# Keyboard.net
KiCad netlist of a schematic drawn in Altium Designer
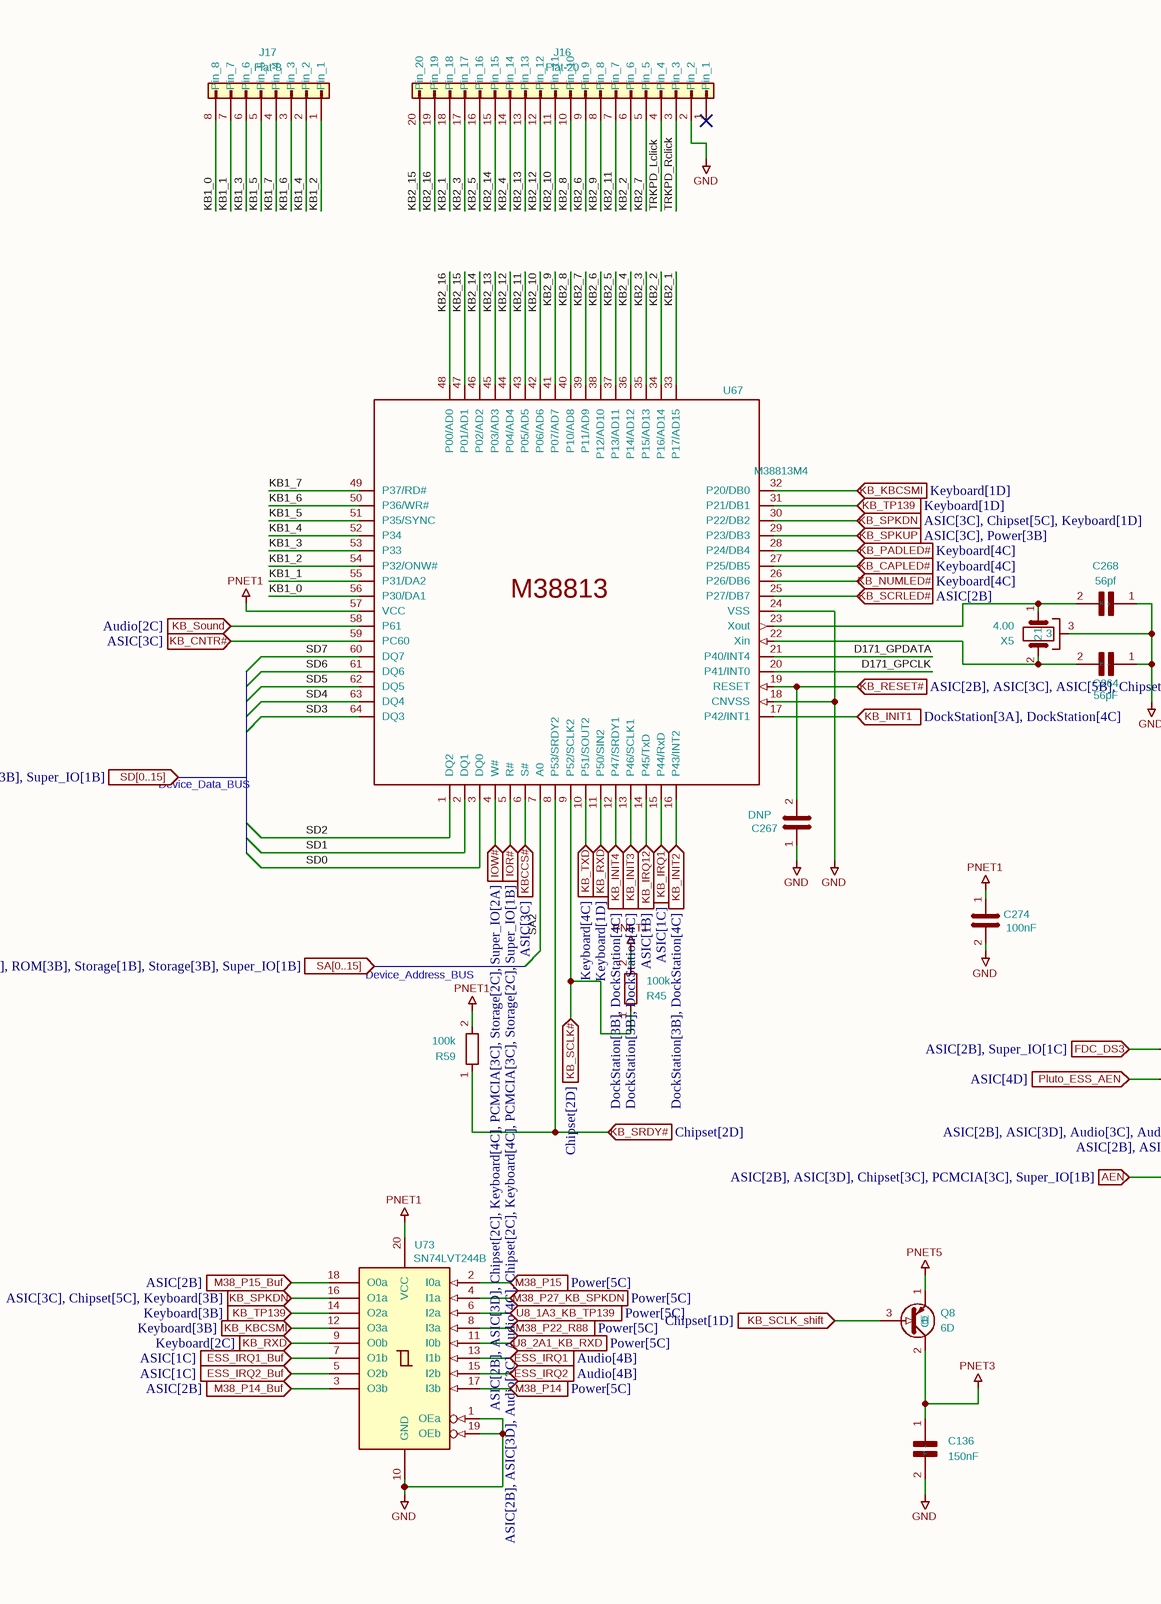
[diagram p0: Keyboard.SchDoc, left]
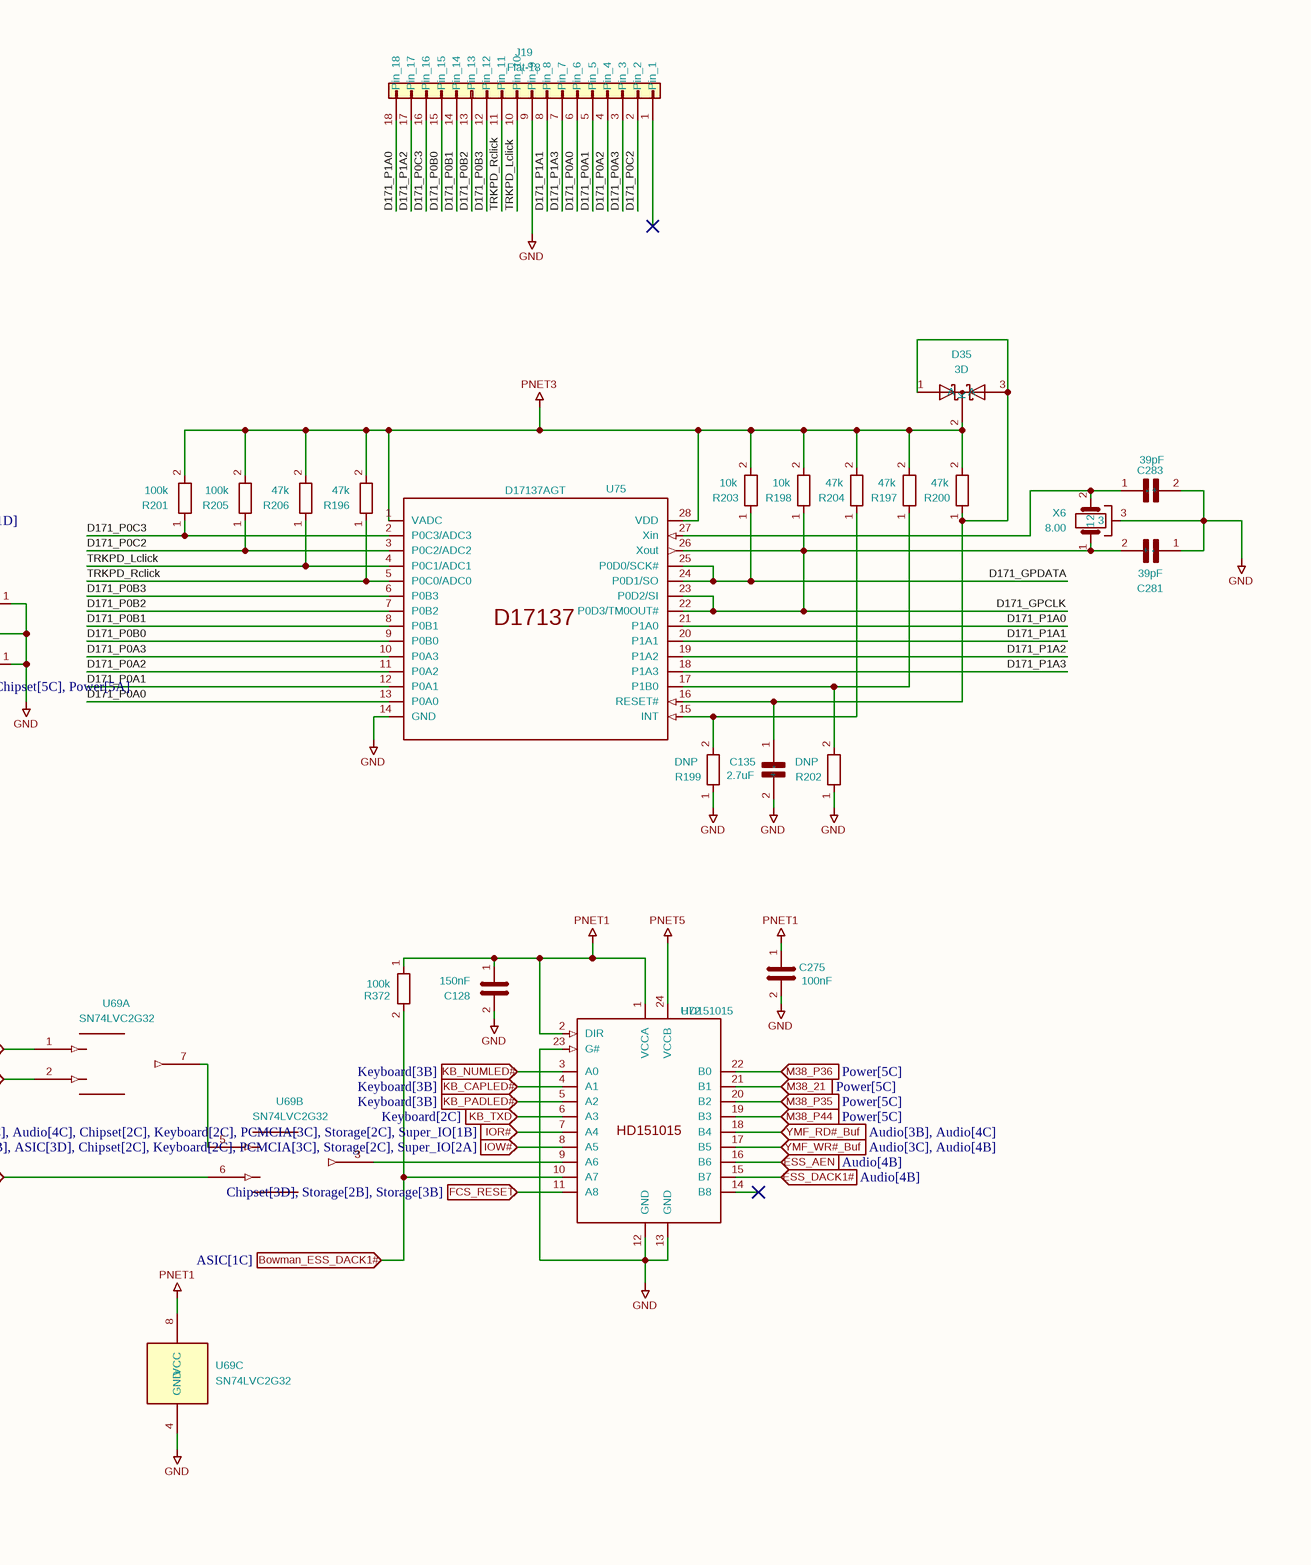
[diagram p1: Keyboard.SchDoc, right]

(export (version "E")
  (design (tool "Eeschema 10.0.6"))
  (components
    (comp (ref "C128") (value "150nF") (footprint "C_0402_1005Metric") (libsource (lib "Device") (part "C")))
    (comp (ref "C135") (value "2.7uF") (footprint "C_0805_2012Metric") (libsource (lib "") (part "C_1")))
    (comp (ref "C136")
      (value "150nF")
      (footprint "C_0402_1005Metric")
      (libsource (lib "PCM_Elektuur") (part "C"))
    )
    (comp (ref "C264") (value "56pF") (footprint "C_0402_1005Metric") (libsource (lib "") (part "C_1")))
    (comp (ref "C267") (value "DNP") (footprint "C_0402_1005Metric") (libsource (lib "Device") (part "C")))
    (comp (ref "C268")
      (value "56pf")
      (footprint "C_0402_1005Metric")
      (libsource (lib "PCM_Elektuur") (part "C"))
    )
    (comp (ref "C274") (value "100nF") (footprint "C_0402_1005Metric") (libsource (lib "Device") (part "C")))
    (comp (ref "C275") (value "100nF") (footprint "C_0402_1005Metric") (libsource (lib "Device") (part "C")))
    (comp (ref "C281") (value "39pF") (footprint "C_0402_1005Metric") (libsource (lib "") (part "C_1")))
    (comp (ref "C283") (value "39pF") (footprint "C_0402_1005Metric") (libsource (lib "") (part "C_2")))
    (comp (ref "D35")
      (value "3D")
      (footprint "3D")
      (libsource (lib "Device") (part "D_Schottky_Dual_CommonCathode_AKA"))
    )
    (comp (ref "J16")
      (value "Flat-20")
      (footprint "Flat-20")
      (libsource (lib "Connector_Generic") (part "Conn_01x20"))
    )
    (comp (ref "J17")
      (value "Flat-8")
      (footprint "Flat-8")
      (libsource (lib "Connector_Generic") (part "Conn_01x08"))
    )
    (comp (ref "J19")
      (value "Flat-18")
      (footprint "Flat-18")
      (libsource (lib "Connector_Generic") (part "Conn_01x18"))
    )
    (comp (ref "Q8")
      (value "6D")
      (footprint "3D")
      (libsource (lib "PCM_Transistor_BJT_AKL") (part "Q_PNP_Generic_ECB"))
    )
    (comp (ref "R45") (value "100k") (footprint "R_0402_1005Metric") (libsource (lib "") (part "R_1")))
    (comp (ref "R59") (value "100k") (footprint "R_0402_1005Metric") (libsource (lib "Device") (part "R")))
    (comp (ref "R196") (value "47k") (footprint "R_0402_1005Metric") (libsource (lib "Device") (part "R")))
    (comp (ref "R197") (value "47k") (footprint "R_0402_1005Metric") (libsource (lib "Device") (part "R")))
    (comp (ref "R198") (value "10k") (footprint "R_0402_1005Metric") (libsource (lib "Device") (part "R")))
    (comp (ref "R199") (value "DNP") (footprint "R_0402_1005Metric") (libsource (lib "Device") (part "R")))
    (comp (ref "R200") (value "47k") (footprint "R_0402_1005Metric") (libsource (lib "Device") (part "R")))
    (comp (ref "R201") (value "100k") (footprint "R_0402_1005Metric") (libsource (lib "Device") (part "R")))
    (comp (ref "R202") (value "DNP") (footprint "R_0402_1005Metric") (libsource (lib "Device") (part "R")))
    (comp (ref "R203") (value "10k") (footprint "R_0402_1005Metric") (libsource (lib "Device") (part "R")))
    (comp (ref "R204") (value "47k") (footprint "R_0402_1005Metric") (libsource (lib "Device") (part "R")))
    (comp (ref "R205") (value "100k") (footprint "R_0402_1005Metric") (libsource (lib "Device") (part "R")))
    (comp (ref "R206") (value "47k") (footprint "R_0402_1005Metric") (libsource (lib "Device") (part "R")))
    (comp (ref "R372") (value "100k") (footprint "R_0402_1005Metric") (libsource (lib "") (part "R_2")))
    (comp (ref "U67") (value "M38813M4") (footprint "QFN64") (libsource (lib "PC110") (part "M38813")))
    (comp (ref "U69")
      (value "SN74LVC2G32")
      (footprint "SSOP-8_2.95x2.8mm_P0.65mm")
      (libsource (lib "74xGxx") (part "74LVC2G32"))
    )
    (comp (ref "U72")
      (value "HD151015")
      (footprint "SSOP-24_5.3x8.2mm_P0.65mm")
      (libsource (lib "PC110") (part "HD151015"))
    )
    (comp (ref "U73")
      (value "SN74LVT244B")
      (footprint "TSSOP-20_4.4x6.5mm_P0.65mm")
      (libsource (lib "74xx") (part "74LS244"))
    )
    (comp (ref "U75") (value "D17137AGT") (footprint "SSOP-28") (libsource (lib "PC110") (part "D17137")))
    (comp (ref "X5") (value "4.00") (footprint "XTAL-5") (libsource (lib "") (part "Crystal_GND3_1")))
    (comp (ref "X6") (value "8.00") (footprint "XTAL-4") (libsource (lib "Device") (part "Crystal_GND3")))
  )
  (nets
    (net (code "24") (name "/AEN") (class "Default")
      (node (ref "U69") (pin "6") (pinfunction "6_6") (pintype "input"))
    )
    (net (code "25") (name "/Bowman_ESS_DACK1#") (class "Default")
      (node (ref "R372") (pin "2") (pinfunction "2_2") (pintype "passive"))
      (node (ref "U72") (pin "10") (pinfunction "A7_10") (pintype "bidirectional"))
    )
    (net (code "26") (name "/D171_GPCLK") (class "Default")
      (node (ref "C281") (pin "2") (pinfunction "-_2") (pintype "passive"))
      (node (ref "R198") (pin "1") (pinfunction "1_1") (pintype "passive"))
      (node (ref "U67") (pin "20") (pinfunction "P41/INT0_20") (pintype "bidirectional"))
      (node (ref "U75") (pin "22") (pinfunction "P0D3/TM0OUT#_22") (pintype "bidirectional"))
      (node (ref "U75") (pin "23") (pinfunction "P0D2/SI_23") (pintype "bidirectional"))
      (node (ref "U75") (pin "26") (pinfunction "Xout_26") (pintype "output"))
      (node (ref "X6") (pin "1") (pinfunction "1_1") (pintype "passive"))
    )
    (net (code "27") (name "/D171_GPDATA") (class "Default")
      (node (ref "R203") (pin "1") (pinfunction "1_1") (pintype "passive"))
      (node (ref "U67") (pin "21") (pinfunction "P40/INT4_21") (pintype "bidirectional"))
      (node (ref "U75") (pin "24") (pinfunction "P0D1/SO_24") (pintype "bidirectional"))
      (node (ref "U75") (pin "25") (pinfunction "P0D0/SCK#_25") (pintype "bidirectional"))
    )
    (net (code "28") (name "/D171_P0A0") (class "Default")
      (node (ref "J19") (pin "6") (pinfunction "Pin_6_6") (pintype "passive"))
      (node (ref "U75") (pin "13") (pinfunction "P0A0_13") (pintype "bidirectional"))
    )
    (net (code "29") (name "/D171_P0A1") (class "Default")
      (node (ref "J19") (pin "5") (pinfunction "Pin_5_5") (pintype "passive"))
      (node (ref "U75") (pin "12") (pinfunction "P0A1_12") (pintype "bidirectional"))
    )
    (net (code "30") (name "/D171_P0A2") (class "Default")
      (node (ref "J19") (pin "4") (pinfunction "Pin_4_4") (pintype "passive"))
      (node (ref "U75") (pin "11") (pinfunction "P0A2_11") (pintype "bidirectional"))
    )
    (net (code "31") (name "/D171_P0A3") (class "Default")
      (node (ref "J19") (pin "3") (pinfunction "Pin_3_3") (pintype "passive"))
      (node (ref "U75") (pin "10") (pinfunction "P0A3_10") (pintype "bidirectional"))
    )
    (net (code "32") (name "/D171_P0B0") (class "Default")
      (node (ref "J19") (pin "15") (pinfunction "Pin_15_15") (pintype "passive"))
      (node (ref "U75") (pin "9") (pinfunction "P0B0_9") (pintype "bidirectional"))
    )
    (net (code "33") (name "/D171_P0B1") (class "Default")
      (node (ref "J19") (pin "14") (pinfunction "Pin_14_14") (pintype "passive"))
      (node (ref "U75") (pin "8") (pinfunction "P0B1_8") (pintype "bidirectional"))
    )
    (net (code "34") (name "/D171_P0B2") (class "Default")
      (node (ref "J19") (pin "13") (pinfunction "Pin_13_13") (pintype "passive"))
      (node (ref "U75") (pin "7") (pinfunction "P0B2_7") (pintype "bidirectional"))
    )
    (net (code "35") (name "/D171_P0B3") (class "Default")
      (node (ref "J19") (pin "12") (pinfunction "Pin_12_12") (pintype "passive"))
      (node (ref "U75") (pin "6") (pinfunction "P0B3_6") (pintype "bidirectional"))
    )
    (net (code "36") (name "/D171_P0C2") (class "Default")
      (node (ref "J19") (pin "2") (pinfunction "Pin_2_2") (pintype "passive"))
      (node (ref "R205") (pin "1") (pinfunction "1_1") (pintype "passive"))
      (node (ref "U75") (pin "3") (pinfunction "P0C2/ADC2_3") (pintype "bidirectional"))
    )
    (net (code "37") (name "/D171_P0C3") (class "Default")
      (node (ref "J19") (pin "16") (pinfunction "Pin_16_16") (pintype "passive"))
      (node (ref "R201") (pin "1") (pinfunction "1_1") (pintype "passive"))
      (node (ref "U75") (pin "2") (pinfunction "P0C3/ADC3_2") (pintype "bidirectional"))
    )
    (net (code "38") (name "/D171_P1A0") (class "Default")
      (node (ref "J19") (pin "18") (pinfunction "Pin_18_18") (pintype "passive"))
      (node (ref "U75") (pin "21") (pinfunction "P1A0_21") (pintype "bidirectional"))
    )
    (net (code "39") (name "/D171_P1A1") (class "Default")
      (node (ref "J19") (pin "8") (pinfunction "Pin_8_8") (pintype "passive"))
      (node (ref "U75") (pin "20") (pinfunction "P1A1_20") (pintype "bidirectional"))
    )
    (net (code "40") (name "/D171_P1A2") (class "Default")
      (node (ref "J19") (pin "17") (pinfunction "Pin_17_17") (pintype "passive"))
      (node (ref "U75") (pin "19") (pinfunction "P1A2_19") (pintype "bidirectional"))
    )
    (net (code "41") (name "/D171_P1A3") (class "Default")
      (node (ref "J19") (pin "7") (pinfunction "Pin_7_7") (pintype "passive"))
      (node (ref "U75") (pin "18") (pinfunction "P1A3_18") (pintype "bidirectional"))
    )
    (net (code "42") (name "/ESS_AEN") (class "Default")
      (node (ref "U72") (pin "16") (pinfunction "B6_16") (pintype "bidirectional"))
    )
    (net (code "43") (name "/ESS_DACK1#") (class "Default")
      (node (ref "U72") (pin "15") (pinfunction "B7_15") (pintype "bidirectional"))
    )
    (net (code "44") (name "/ESS_IRQ1") (class "Default")
      (node (ref "U73") (pin "13") (pinfunction "I1b_13") (pintype "input"))
    )
    (net (code "45") (name "/ESS_IRQ1_Buf") (class "Default")
      (node (ref "U73") (pin "7") (pinfunction "O1b_7") (pintype "tri_state"))
    )
    (net (code "46") (name "/ESS_IRQ2") (class "Default")
      (node (ref "U73") (pin "15") (pinfunction "I2b_15") (pintype "input"))
    )
    (net (code "47") (name "/ESS_IRQ2_Buf") (class "Default")
      (node (ref "U73") (pin "5") (pinfunction "O2b_5") (pintype "tri_state"))
    )
    (net (code "48") (name "/FCS_RESET") (class "Default")
      (node (ref "U72") (pin "11") (pinfunction "A8_11") (pintype "bidirectional"))
    )
    (net (code "49") (name "/FDC_DS3") (class "Default")
      (node (ref "U69") (pin "1") (pinfunction "1_1") (pintype "input"))
    )
    (net (code "50") (name "/IOR#") (class "Default")
      (node (ref "U67") (pin "5") (pinfunction "R#_5") (pintype "bidirectional"))
      (node (ref "U72") (pin "7") (pinfunction "A4_7") (pintype "bidirectional"))
    )
    (net (code "51") (name "/IOW#") (class "Default")
      (node (ref "U67") (pin "4") (pinfunction "W#_4") (pintype "bidirectional"))
      (node (ref "U72") (pin "8") (pinfunction "A5_8") (pintype "bidirectional"))
    )
    (net (code "52") (name "/KB1_0") (class "Default")
      (node (ref "J17") (pin "8") (pinfunction "Pin_8_8") (pintype "passive"))
      (node (ref "U67") (pin "56") (pinfunction "P30/DA1_56") (pintype "bidirectional"))
    )
    (net (code "53") (name "/KB1_1") (class "Default")
      (node (ref "J17") (pin "7") (pinfunction "Pin_7_7") (pintype "passive"))
      (node (ref "U67") (pin "55") (pinfunction "P31/DA2_55") (pintype "bidirectional"))
    )
    (net (code "54") (name "/KB1_2") (class "Default")
      (node (ref "J17") (pin "1") (pinfunction "Pin_1_1") (pintype "passive"))
      (node (ref "U67") (pin "54") (pinfunction "P32/ONW#_54") (pintype "bidirectional"))
    )
    (net (code "55") (name "/KB1_3") (class "Default")
      (node (ref "J17") (pin "6") (pinfunction "Pin_6_6") (pintype "passive"))
      (node (ref "U67") (pin "53") (pinfunction "P33_53") (pintype "bidirectional"))
    )
    (net (code "56") (name "/KB1_4") (class "Default")
      (node (ref "J17") (pin "2") (pinfunction "Pin_2_2") (pintype "passive"))
      (node (ref "U67") (pin "52") (pinfunction "P34_52") (pintype "bidirectional"))
    )
    (net (code "57") (name "/KB1_5") (class "Default")
      (node (ref "J17") (pin "5") (pinfunction "Pin_5_5") (pintype "passive"))
      (node (ref "U67") (pin "51") (pinfunction "P35/SYNC_51") (pintype "bidirectional"))
    )
    (net (code "58") (name "/KB1_6") (class "Default")
      (node (ref "J17") (pin "3") (pinfunction "Pin_3_3") (pintype "passive"))
      (node (ref "U67") (pin "50") (pinfunction "P36/WR#_50") (pintype "bidirectional"))
    )
    (net (code "59") (name "/KB1_7") (class "Default")
      (node (ref "J17") (pin "4") (pinfunction "Pin_4_4") (pintype "passive"))
      (node (ref "U67") (pin "49") (pinfunction "P37/RD#_49") (pintype "bidirectional"))
    )
    (net (code "60") (name "/KB2_1") (class "Default")
      (node (ref "J16") (pin "18") (pinfunction "Pin_18_18") (pintype "passive"))
      (node (ref "U67") (pin "33") (pinfunction "P17/AD15_33") (pintype "bidirectional"))
    )
    (net (code "61") (name "/KB2_2") (class "Default")
      (node (ref "J16") (pin "6") (pinfunction "Pin_6_6") (pintype "passive"))
      (node (ref "U67") (pin "34") (pinfunction "P16/AD14_34") (pintype "bidirectional"))
    )
    (net (code "62") (name "/KB2_3") (class "Default")
      (node (ref "J16") (pin "17") (pinfunction "Pin_17_17") (pintype "passive"))
      (node (ref "U67") (pin "35") (pinfunction "P15/AD13_35") (pintype "bidirectional"))
    )
    (net (code "63") (name "/KB2_4") (class "Default")
      (node (ref "J16") (pin "14") (pinfunction "Pin_14_14") (pintype "passive"))
      (node (ref "U67") (pin "36") (pinfunction "P14/AD12_36") (pintype "bidirectional"))
    )
    (net (code "64") (name "/KB2_5") (class "Default")
      (node (ref "J16") (pin "16") (pinfunction "Pin_16_16") (pintype "passive"))
      (node (ref "U67") (pin "37") (pinfunction "P13/AD11_37") (pintype "bidirectional"))
    )
    (net (code "65") (name "/KB2_6") (class "Default")
      (node (ref "J16") (pin "9") (pinfunction "Pin_9_9") (pintype "passive"))
      (node (ref "U67") (pin "38") (pinfunction "P12/AD10_38") (pintype "bidirectional"))
    )
    (net (code "66") (name "/KB2_7") (class "Default")
      (node (ref "J16") (pin "5") (pinfunction "Pin_5_5") (pintype "passive"))
      (node (ref "U67") (pin "39") (pinfunction "P11/AD9_39") (pintype "bidirectional"))
    )
    (net (code "67") (name "/KB2_8") (class "Default")
      (node (ref "J16") (pin "10") (pinfunction "Pin_10_10") (pintype "passive"))
      (node (ref "U67") (pin "40") (pinfunction "P10/AD8_40") (pintype "bidirectional"))
    )
    (net (code "68") (name "/KB2_9") (class "Default")
      (node (ref "J16") (pin "8") (pinfunction "Pin_8_8") (pintype "passive"))
      (node (ref "U67") (pin "41") (pinfunction "P07/AD7_41") (pintype "bidirectional"))
    )
    (net (code "69") (name "/KB2_10") (class "Default")
      (node (ref "J16") (pin "11") (pinfunction "Pin_11_11") (pintype "passive"))
      (node (ref "U67") (pin "42") (pinfunction "P06/AD6_42") (pintype "bidirectional"))
    )
    (net (code "70") (name "/KB2_11") (class "Default")
      (node (ref "J16") (pin "7") (pinfunction "Pin_7_7") (pintype "passive"))
      (node (ref "U67") (pin "43") (pinfunction "P05/AD5_43") (pintype "bidirectional"))
    )
    (net (code "71") (name "/KB2_12") (class "Default")
      (node (ref "J16") (pin "12") (pinfunction "Pin_12_12") (pintype "passive"))
      (node (ref "U67") (pin "44") (pinfunction "P04/AD4_44") (pintype "bidirectional"))
    )
    (net (code "72") (name "/KB2_13") (class "Default")
      (node (ref "J16") (pin "13") (pinfunction "Pin_13_13") (pintype "passive"))
      (node (ref "U67") (pin "45") (pinfunction "P03/AD3_45") (pintype "bidirectional"))
    )
    (net (code "73") (name "/KB2_14") (class "Default")
      (node (ref "J16") (pin "15") (pinfunction "Pin_15_15") (pintype "passive"))
      (node (ref "U67") (pin "46") (pinfunction "P02/AD2_46") (pintype "bidirectional"))
    )
    (net (code "74") (name "/KB2_15") (class "Default")
      (node (ref "J16") (pin "20") (pinfunction "Pin_20_20") (pintype "passive"))
      (node (ref "U67") (pin "47") (pinfunction "P01/AD1_47") (pintype "bidirectional"))
    )
    (net (code "75") (name "/KB2_16") (class "Default")
      (node (ref "J16") (pin "19") (pinfunction "Pin_19_19") (pintype "passive"))
      (node (ref "U67") (pin "48") (pinfunction "P00/AD0_48") (pintype "bidirectional"))
    )
    (net (code "76") (name "/KBCCS#") (class "Default")
      (node (ref "U67") (pin "6") (pinfunction "S#_6") (pintype "bidirectional"))
    )
    (net (code "77") (name "/KB_CAPLED#") (class "Default")
      (node (ref "U67") (pin "27") (pinfunction "P25/DB5_27") (pintype "bidirectional"))
      (node (ref "U72") (pin "4") (pinfunction "A1_4") (pintype "bidirectional"))
    )
    (net (code "78") (name "/KB_CNTR#") (class "Default")
      (node (ref "U67") (pin "59") (pinfunction "PC60_59") (pintype "bidirectional"))
    )
    (net (code "79") (name "/KB_INIT1") (class "Default")
      (node (ref "U67") (pin "17") (pinfunction "P42/INT1_17") (pintype "bidirectional"))
    )
    (net (code "80") (name "/KB_INIT2") (class "Default")
      (node (ref "U67") (pin "16") (pinfunction "P43/INT2_16") (pintype "bidirectional"))
    )
    (net (code "81") (name "/KB_INIT3") (class "Default")
      (node (ref "U67") (pin "13") (pinfunction "P46/SCLK1_13") (pintype "bidirectional"))
    )
    (net (code "82") (name "/KB_INIT4") (class "Default")
      (node (ref "U67") (pin "12") (pinfunction "P47/SRDY1_12") (pintype "bidirectional"))
    )
    (net (code "83") (name "/KB_IRQ1") (class "Default")
      (node (ref "U67") (pin "15") (pinfunction "P44/RxD_15") (pintype "bidirectional"))
    )
    (net (code "84") (name "/KB_IRQ12") (class "Default")
      (node (ref "U67") (pin "14") (pinfunction "P45/TxD_14") (pintype "bidirectional"))
    )
    (net (code "85") (name "/KB_KBCSMI") (class "Default")
      (node (ref "U67") (pin "32") (pinfunction "P20/DB0_32") (pintype "bidirectional"))
      (node (ref "U73") (pin "12") (pinfunction "O3a_12") (pintype "tri_state"))
    )
    (net (code "86") (name "/KB_NUMLED#") (class "Default")
      (node (ref "U67") (pin "26") (pinfunction "P26/DB6_26") (pintype "bidirectional"))
      (node (ref "U72") (pin "3") (pinfunction "A0_3") (pintype "bidirectional"))
    )
    (net (code "87") (name "/KB_PADLED#") (class "Default")
      (node (ref "U67") (pin "28") (pinfunction "P24/DB4_28") (pintype "bidirectional"))
      (node (ref "U72") (pin "5") (pinfunction "A2_5") (pintype "bidirectional"))
    )
    (net (code "88") (name "/KB_RESET#") (class "Default")
      (node (ref "C267") (pin "2") (pinfunction "2_2") (pintype "passive"))
      (node (ref "U67") (pin "19") (pinfunction "RESET_19") (pintype "input"))
    )
    (net (code "89") (name "/KB_RXD") (class "Default")
      (node (ref "U67") (pin "11") (pinfunction "P50/SIN2_11") (pintype "bidirectional"))
      (node (ref "U73") (pin "9") (pinfunction "O0b_9") (pintype "tri_state"))
    )
    (net (code "90") (name "/KB_SCLK#") (class "Default")
      (node (ref "R45") (pin "1") (pinfunction "1_1") (pintype "passive"))
      (node (ref "U67") (pin "9") (pinfunction "P52/SCLK2_9") (pintype "bidirectional"))
    )
    (net (code "91") (name "/KB_SCLK_shift") (class "Default")
      (node (ref "Q8") (pin "3") (pinfunction "B_3") (pintype "input"))
    )
    (net (code "92") (name "/KB_SCRLED#") (class "Default")
      (node (ref "U67") (pin "25") (pinfunction "P27/DB7_25") (pintype "bidirectional"))
    )
    (net (code "93") (name "/KB_SPKDN") (class "Default")
      (node (ref "U67") (pin "30") (pinfunction "P22/DB2_30") (pintype "bidirectional"))
      (node (ref "U73") (pin "16") (pinfunction "O1a_16") (pintype "tri_state"))
    )
    (net (code "94") (name "/KB_SPKUP") (class "Default")
      (node (ref "U67") (pin "29") (pinfunction "P23/DB3_29") (pintype "bidirectional"))
    )
    (net (code "95") (name "/KB_SRDY#") (class "Default")
      (node (ref "R59") (pin "1") (pinfunction "1_1") (pintype "passive"))
      (node (ref "U67") (pin "8") (pinfunction "P53/SRDY2_8") (pintype "bidirectional"))
    )
    (net (code "96") (name "/KB_Sound") (class "Default")
      (node (ref "U67") (pin "58") (pinfunction "P61_58") (pintype "bidirectional"))
    )
    (net (code "97") (name "/KB_TP139") (class "Default")
      (node (ref "U67") (pin "31") (pinfunction "P21/DB1_31") (pintype "bidirectional"))
      (node (ref "U73") (pin "14") (pinfunction "O2a_14") (pintype "tri_state"))
    )
    (net (code "98") (name "/KB_TXD") (class "Default")
      (node (ref "U67") (pin "10") (pinfunction "P51/SOUT2_10") (pintype "bidirectional"))
      (node (ref "U72") (pin "6") (pinfunction "A3_6") (pintype "bidirectional"))
    )
    (net (code "99") (name "/M38_21") (class "Default")
      (node (ref "U72") (pin "21") (pinfunction "B1_21") (pintype "bidirectional"))
    )
    (net (code "100") (name "/M38_P14") (class "Default")
      (node (ref "U73") (pin "17") (pinfunction "I3b_17") (pintype "input"))
    )
    (net (code "101") (name "/M38_P14_Buf") (class "Default")
      (node (ref "U73") (pin "3") (pinfunction "O3b_3") (pintype "tri_state"))
    )
    (net (code "102") (name "/M38_P15") (class "Default")
      (node (ref "U73") (pin "2") (pinfunction "I0a_2") (pintype "input"))
    )
    (net (code "103") (name "/M38_P15_Buf") (class "Default")
      (node (ref "U73") (pin "18") (pinfunction "O0a_18") (pintype "tri_state"))
    )
    (net (code "104") (name "/M38_P22_R88") (class "Default")
      (node (ref "U73") (pin "8") (pinfunction "I3a_8") (pintype "input"))
    )
    (net (code "105") (name "/M38_P27_KB_SPKDN") (class "Default")
      (node (ref "U73") (pin "4") (pinfunction "I1a_4") (pintype "input"))
    )
    (net (code "106") (name "/M38_P35") (class "Default")
      (node (ref "U72") (pin "20") (pinfunction "B2_20") (pintype "bidirectional"))
    )
    (net (code "107") (name "/M38_P36") (class "Default")
      (node (ref "U72") (pin "22") (pinfunction "B0_22") (pintype "bidirectional"))
    )
    (net (code "108") (name "/M38_P44") (class "Default")
      (node (ref "U72") (pin "19") (pinfunction "B3_19") (pintype "bidirectional"))
    )
    (net (code "109") (name "/Pluto_ESS_AEN") (class "Default")
      (node (ref "U69") (pin "2") (pinfunction "2_2") (pintype "input"))
    )
    (net (code "110") (name "/SA2") (class "Default")
      (node (ref "U67") (pin "7") (pinfunction "A0_7") (pintype "bidirectional"))
    )
    (net (code "112") (name "/SD0") (class "Default")
      (node (ref "U67") (pin "3") (pinfunction "DQ0_3") (pintype "bidirectional"))
    )
    (net (code "113") (name "/SD1") (class "Default")
      (node (ref "U67") (pin "2") (pinfunction "DQ1_2") (pintype "bidirectional"))
    )
    (net (code "114") (name "/SD2") (class "Default")
      (node (ref "U67") (pin "1") (pinfunction "DQ2_1") (pintype "bidirectional"))
    )
    (net (code "115") (name "/SD3") (class "Default")
      (node (ref "U67") (pin "64") (pinfunction "DQ3_64") (pintype "bidirectional"))
    )
    (net (code "116") (name "/SD4") (class "Default")
      (node (ref "U67") (pin "63") (pinfunction "DQ4_63") (pintype "bidirectional"))
    )
    (net (code "117") (name "/SD5") (class "Default")
      (node (ref "U67") (pin "62") (pinfunction "DQ5_62") (pintype "bidirectional"))
    )
    (net (code "118") (name "/SD6") (class "Default")
      (node (ref "U67") (pin "61") (pinfunction "DQ6_61") (pintype "bidirectional"))
    )
    (net (code "119") (name "/SD7") (class "Default")
      (node (ref "U67") (pin "60") (pinfunction "DQ7_60") (pintype "bidirectional"))
    )
    (net (code "121") (name "/TRKPD_Lclick") (class "Default")
      (node (ref "J16") (pin "4") (pinfunction "Pin_4_4") (pintype "passive"))
      (node (ref "J19") (pin "10") (pinfunction "Pin_10_10") (pintype "passive"))
      (node (ref "R206") (pin "1") (pinfunction "1_1") (pintype "passive"))
      (node (ref "U75") (pin "4") (pinfunction "P0C1/ADC1_4") (pintype "bidirectional"))
    )
    (net (code "122") (name "/TRKPD_Rclick") (class "Default")
      (node (ref "J16") (pin "3") (pinfunction "Pin_3_3") (pintype "passive"))
      (node (ref "J19") (pin "11") (pinfunction "Pin_11_11") (pintype "passive"))
      (node (ref "R196") (pin "1") (pinfunction "1_1") (pintype "passive"))
      (node (ref "U75") (pin "5") (pinfunction "P0C0/ADC0_5") (pintype "bidirectional"))
    )
    (net (code "123") (name "/U8_1A3_KB_TP139") (class "Default")
      (node (ref "U73") (pin "6") (pinfunction "I2a_6") (pintype "input"))
    )
    (net (code "124") (name "/U8_2A1_KB_RXD") (class "Default")
      (node (ref "U73") (pin "11") (pinfunction "I0b_11") (pintype "input"))
    )
    (net (code "125") (name "/YMF_RD#_Buf") (class "Default")
      (node (ref "U72") (pin "18") (pinfunction "B4_18") (pintype "bidirectional"))
    )
    (net (code "126") (name "/YMF_WR#_Buf") (class "Default")
      (node (ref "U72") (pin "17") (pinfunction "B5_17") (pintype "bidirectional"))
    )
    (net (code "127") (name "GND") (class "Default")
      (node (ref "C128") (pin "2") (pinfunction "2_2") (pintype "passive"))
      (node (ref "C135") (pin "2") (pinfunction "-_2") (pintype "passive"))
      (node (ref "C136") (pin "2") (pinfunction "-_2") (pintype "passive"))
      (node (ref "C264") (pin "1") (pinfunction "+_1") (pintype "passive"))
      (node (ref "C267") (pin "1") (pinfunction "1_1") (pintype "passive"))
      (node (ref "C268") (pin "1") (pinfunction "+_1") (pintype "passive"))
      (node (ref "C274") (pin "2") (pinfunction "2_2") (pintype "passive"))
      (node (ref "C275") (pin "2") (pinfunction "2_2") (pintype "passive"))
      (node (ref "C281") (pin "1") (pinfunction "+_1") (pintype "passive"))
      (node (ref "C283") (pin "2") (pinfunction "-_2") (pintype "passive"))
      (node (ref "J16") (pin "2") (pinfunction "Pin_2_2") (pintype "passive"))
      (node (ref "J19") (pin "9") (pinfunction "Pin_9_9") (pintype "passive"))
      (node (ref "R199") (pin "1") (pinfunction "1_1") (pintype "passive"))
      (node (ref "R202") (pin "1") (pinfunction "1_1") (pintype "passive"))
      (node (ref "U67") (pin "18") (pinfunction "CNVSS_18") (pintype "input"))
      (node (ref "U67") (pin "24") (pinfunction "VSS_24") (pintype "power_in"))
      (node (ref "U69") (pin "4") (pinfunction "GND_4") (pintype "power_in"))
      (node (ref "U72") (pin "12") (pinfunction "GND_12") (pintype "power_in"))
      (node (ref "U72") (pin "13") (pinfunction "GND_13") (pintype "power_in"))
      (node (ref "U72") (pin "23") (pinfunction "G#_23") (pintype "input"))
      (node (ref "U73") (pin "1") (pinfunction "OEa_1") (pintype "input"))
      (node (ref "U73") (pin "10") (pinfunction "GND_10") (pintype "power_in"))
      (node (ref "U73") (pin "19") (pinfunction "OEb_19") (pintype "input"))
      (node (ref "U75") (pin "14") (pinfunction "GND_14") (pintype "power_in"))
      (node (ref "X5") (pin "3") (pinfunction "3_3") (pintype "passive"))
      (node (ref "X6") (pin "3") (pinfunction "3_3") (pintype "passive"))
    )
    (net (code "128") (name "Net-(C135-+)") (class "Default")
      (node (ref "C135") (pin "1") (pinfunction "+_1") (pintype "passive"))
      (node (ref "D35") (pin "1") (pinfunction "A_1") (pintype "passive"))
      (node (ref "D35") (pin "3") (pinfunction "A_3") (pintype "passive"))
      (node (ref "R200") (pin "1") (pinfunction "1_1") (pintype "passive"))
      (node (ref "U75") (pin "16") (pinfunction "RESET#_16") (pintype "input"))
    )
    (net (code "129") (name "Net-(C264--)") (class "Default")
      (node (ref "C264") (pin "2") (pinfunction "-_2") (pintype "passive"))
      (node (ref "U67") (pin "22") (pinfunction "Xin_22") (pintype "input"))
      (node (ref "X5") (pin "2") (pinfunction "2_2") (pintype "passive"))
    )
    (net (code "130") (name "Net-(C268--)") (class "Default")
      (node (ref "C268") (pin "2") (pinfunction "-_2") (pintype "passive"))
      (node (ref "U67") (pin "23") (pinfunction "Xout_23") (pintype "output"))
      (node (ref "X5") (pin "1") (pinfunction "1_1") (pintype "passive"))
    )
    (net (code "131") (name "Net-(C283-+)") (class "Default")
      (node (ref "C283") (pin "1") (pinfunction "+_1") (pintype "passive"))
      (node (ref "U75") (pin "27") (pinfunction "Xin_27") (pintype "input"))
      (node (ref "X6") (pin "2") (pinfunction "2_2") (pintype "passive"))
    )
    (net (code "132") (name "Net-(U69-Pad5)") (class "Default")
      (node (ref "U69") (pin "5") (pinfunction "5_5") (pintype "input"))
      (node (ref "U69") (pin "7") (pinfunction "7_7") (pintype "output"))
    )
    (net (code "133") (name "Net-(U72-A6)") (class "Default")
      (node (ref "U69") (pin "3") (pinfunction "3_3") (pintype "output"))
      (node (ref "U72") (pin "9") (pinfunction "A6_9") (pintype "bidirectional"))
    )
    (net (code "134") (name "Net-(U75-INT)") (class "Default")
      (node (ref "R199") (pin "2") (pinfunction "2_2") (pintype "passive"))
      (node (ref "R204") (pin "1") (pinfunction "1_1") (pintype "passive"))
      (node (ref "U75") (pin "15") (pinfunction "INT_15") (pintype "input"))
    )
    (net (code "135") (name "Net-(U75-P1B0)") (class "Default")
      (node (ref "R197") (pin "1") (pinfunction "1_1") (pintype "passive"))
      (node (ref "R202") (pin "2") (pinfunction "2_2") (pintype "passive"))
      (node (ref "U75") (pin "17") (pinfunction "P1B0_17") (pintype "bidirectional"))
    )
    (net (code "136") (name "PNET1") (class "Default")
      (node (ref "C128") (pin "1") (pinfunction "1_1") (pintype "passive"))
      (node (ref "C274") (pin "1") (pinfunction "1_1") (pintype "passive"))
      (node (ref "C275") (pin "1") (pinfunction "1_1") (pintype "passive"))
      (node (ref "R372") (pin "1") (pinfunction "1_1") (pintype "passive"))
      (node (ref "R45") (pin "2") (pinfunction "2_2") (pintype "passive"))
      (node (ref "R59") (pin "2") (pinfunction "2_2") (pintype "passive"))
      (node (ref "U67") (pin "57") (pinfunction "VCC_57") (pintype "power_in"))
      (node (ref "U69") (pin "8") (pinfunction "VCC_8") (pintype "power_in"))
      (node (ref "U72") (pin "1") (pinfunction "VCCA_1") (pintype "power_in"))
      (node (ref "U72") (pin "2") (pinfunction "DIR_2") (pintype "input"))
      (node (ref "U73") (pin "20") (pinfunction "VCC_20") (pintype "power_in"))
    )
    (net (code "137") (name "PNET3") (class "Default")
      (node (ref "C136") (pin "1") (pinfunction "+_1") (pintype "passive"))
      (node (ref "D35") (pin "2") (pinfunction "K_2") (pintype "passive"))
      (node (ref "Q8") (pin "2") (pinfunction "C_2") (pintype "passive"))
      (node (ref "R196") (pin "2") (pinfunction "2_2") (pintype "passive"))
      (node (ref "R197") (pin "2") (pinfunction "2_2") (pintype "passive"))
      (node (ref "R198") (pin "2") (pinfunction "2_2") (pintype "passive"))
      (node (ref "R200") (pin "2") (pinfunction "2_2") (pintype "passive"))
      (node (ref "R201") (pin "2") (pinfunction "2_2") (pintype "passive"))
      (node (ref "R203") (pin "2") (pinfunction "2_2") (pintype "passive"))
      (node (ref "R204") (pin "2") (pinfunction "2_2") (pintype "passive"))
      (node (ref "R205") (pin "2") (pinfunction "2_2") (pintype "passive"))
      (node (ref "R206") (pin "2") (pinfunction "2_2") (pintype "passive"))
      (node (ref "U75") (pin "1") (pinfunction "VADC_1") (pintype "power_in"))
      (node (ref "U75") (pin "28") (pinfunction "VDD_28") (pintype "power_in"))
    )
    (net (code "138") (name "PNET5") (class "Default")
      (node (ref "Q8") (pin "1") (pinfunction "E_1") (pintype "passive"))
      (node (ref "U72") (pin "24") (pinfunction "VCCB_24") (pintype "power_in"))
    )
    (net (code "139") (name "unconnected-(J16-Pin_1-Pad1)") (class "Default")
      (node (ref "J16") (pin "1") (pinfunction "Pin_1_1") (pintype "passive+no_connect"))
    )
    (net (code "140") (name "unconnected-(J19-Pin_1-Pad1)") (class "Default")
      (node (ref "J19") (pin "1") (pinfunction "Pin_1_1") (pintype "passive+no_connect"))
    )
    (net (code "141") (name "unconnected-(U72-B8-Pad14)") (class "Default")
      (node (ref "U72") (pin "14") (pinfunction "B8_14") (pintype "bidirectional+no_connect"))
    )
  )
)
